# CH32V307_V3_0_0.net
KiCad netlist of a schematic drawn in EasyEDA Pro
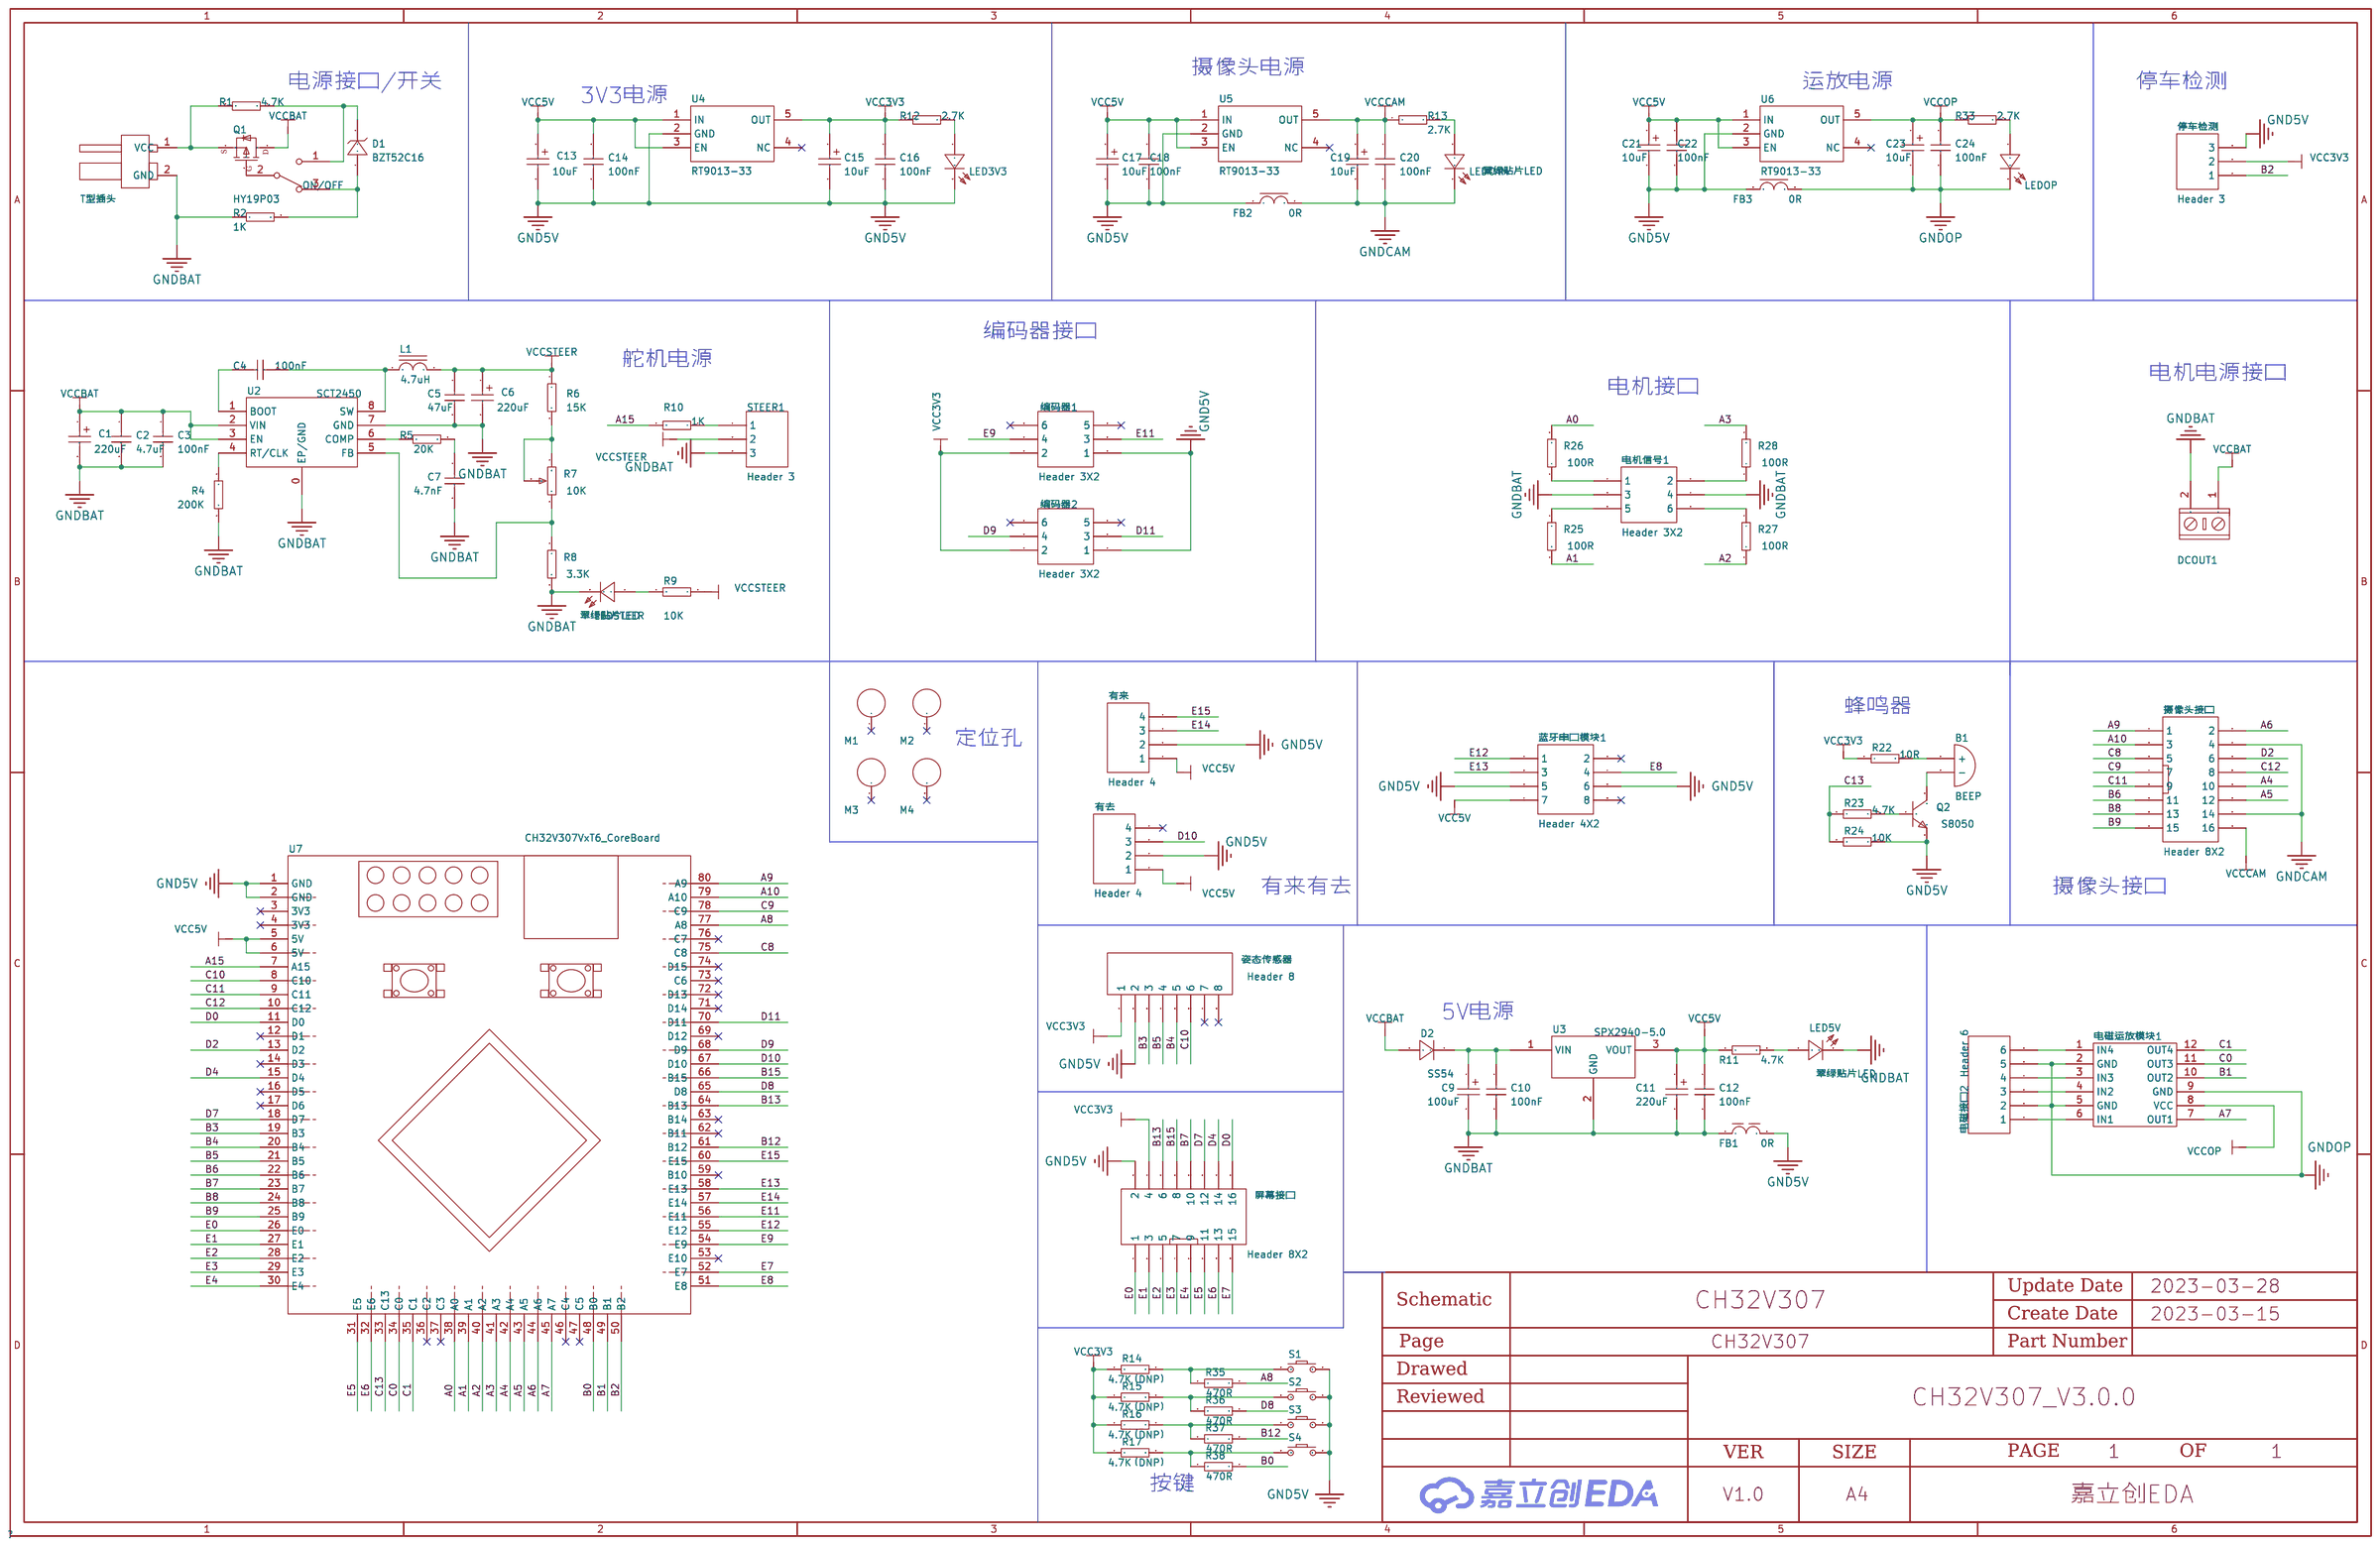
[diagram p0: schematic sheet]

(export (version "E")
  (design (tool "Eeschema 10.0.6"))
  (components
    (comp (ref "B1")
      (value "BEEP")
      (footprint "easyedapro:BEEP 9x5.5mm")
      (libsource (lib "easyedapro") (part "BEEP"))
    )
    (comp (ref "C1")
      (value "220uF")
      (footprint "easyedapro:CAPS6.3")
      (libsource (lib "easyedapro") (part "Cap-Solid_1"))
    )
    (comp (ref "C2")
      (value "4.7nF")
      (footprint "easyedapro:CAPC1608[0603]S-N")
      (libsource (lib "easyedapro") (part "Cap-Chip_3"))
    )
    (comp (ref "C3")
      (value "100nF")
      (footprint "easyedapro:CAPC1608[0603]S-N")
      (libsource (lib "easyedapro") (part "Cap-Chip"))
    )
    (comp (ref "C4")
      (value "100nF")
      (footprint "easyedapro:CAPC1608[0603]S-N")
      (libsource (lib "easyedapro") (part "Cap-Chip"))
    )
    (comp (ref "C5")
      (value "47uF")
      (footprint "easyedapro:CAPC3216[1206]S")
      (libsource (lib "easyedapro") (part "Cap-Chip_2"))
    )
    (comp (ref "C6")
      (value "220uF")
      (footprint "easyedapro:CAPS6.3")
      (libsource (lib "easyedapro") (part "Cap-Solid_1"))
    )
    (comp (ref "C7")
      (value "4.7nF")
      (footprint "easyedapro:CAPC1608[0603]S-N")
      (libsource (lib "easyedapro") (part "Cap-Chip_3"))
    )
    (comp (ref "C9")
      (value "100uF")
      (footprint "easyedapro:CAPS6.3")
      (libsource (lib "easyedapro") (part "Cap-Solid"))
    )
    (comp (ref "C10")
      (value "100nF")
      (footprint "easyedapro:CAPC1608[0603]S-N")
      (libsource (lib "easyedapro") (part "Cap-Chip"))
    )
    (comp (ref "C11")
      (value "220uF")
      (footprint "easyedapro:CAPS6.3")
      (libsource (lib "easyedapro") (part "Cap-Solid_1"))
    )
    (comp (ref "C12")
      (value "100nF")
      (footprint "easyedapro:CAPC1608[0603]S-N")
      (libsource (lib "easyedapro") (part "Cap-Chip"))
    )
    (comp (ref "C13")
      (value "10uF")
      (footprint "easyedapro:CAPT3216")
      (libsource (lib "easyedapro") (part "Cap-Tan"))
    )
    (comp (ref "C14")
      (value "100nF")
      (footprint "easyedapro:CAPC1608[0603]S-N")
      (libsource (lib "easyedapro") (part "Cap-Chip"))
    )
    (comp (ref "C15")
      (value "10uF")
      (footprint "easyedapro:CAPT3216")
      (libsource (lib "easyedapro") (part "Cap-Tan"))
    )
    (comp (ref "C16")
      (value "100nF")
      (footprint "easyedapro:CAPC1608[0603]S-N")
      (libsource (lib "easyedapro") (part "Cap-Chip"))
    )
    (comp (ref "C17")
      (value "10uF")
      (footprint "easyedapro:CAPT3216")
      (libsource (lib "easyedapro") (part "Cap-Tan"))
    )
    (comp (ref "C18")
      (value "100nF")
      (footprint "easyedapro:CAPC1608[0603]S-N")
      (libsource (lib "easyedapro") (part "Cap-Chip"))
    )
    (comp (ref "C19")
      (value "10uF")
      (footprint "easyedapro:CAPT3216")
      (libsource (lib "easyedapro") (part "Cap-Tan"))
    )
    (comp (ref "C20")
      (value "100nF")
      (footprint "easyedapro:CAPC1608[0603]S-N")
      (libsource (lib "easyedapro") (part "Cap-Chip"))
    )
    (comp (ref "C21")
      (value "10uF")
      (footprint "easyedapro:CAPT3216")
      (libsource (lib "easyedapro") (part "Cap-Tan"))
    )
    (comp (ref "C22")
      (value "100nF")
      (footprint "easyedapro:CAPC1608[0603]S-N")
      (libsource (lib "easyedapro") (part "Cap-Chip"))
    )
    (comp (ref "C23")
      (value "10uF")
      (footprint "easyedapro:CAPT3216")
      (libsource (lib "easyedapro") (part "Cap-Tan"))
    )
    (comp (ref "C24")
      (value "100nF")
      (footprint "easyedapro:CAPC1608[0603]S-N")
      (libsource (lib "easyedapro") (part "Cap-Chip"))
    )
    (comp (ref "D1")
      (value "BZT52C16")
      (footprint "easyedapro:SOD-123-L")
      (libsource (lib "easyedapro") (part "Diode TVS Uni-Dir"))
    )
    (comp (ref "D2")
      (value "SS54")
      (footprint "easyedapro:SMA[DO-214AC]")
      (libsource (lib "easyedapro") (part "Diode"))
    )
    (comp (ref "DCOUT1")
      (value "KF/WJ/DG 30x connecter")
      (footprint "easyedapro:KF/WJ/DG 301-2p-5.0mm")
      (libsource (lib "easyedapro") (part "KF/WJ/DG 30x"))
    )
    (comp (ref "FB1")
      (value "0R")
      (footprint "easyedapro:INDC2012[0805]S")
      (libsource (lib "easyedapro") (part "Ind Chip 2"))
    )
    (comp (ref "FB2")
      (value "0R")
      (footprint "easyedapro:INDC2012[0805]S")
      (libsource (lib "easyedapro") (part "Ind-Chip"))
    )
    (comp (ref "FB3")
      (value "0R")
      (footprint "easyedapro:INDC2012[0805]S")
      (libsource (lib "easyedapro") (part "Ind-Chip"))
    )
    (comp (ref "L1")
      (value "4.7uH")
      (footprint "easyedapro:0630 TPC 7*7*3")
      (libsource (lib "easyedapro") (part "Ind-Power"))
    )
    (comp (ref "LED3V3")
      (value "翠绿贴片LED")
      (footprint "easyedapro:LEDC1608(0603)")
      (libsource (lib "easyedapro") (part "LED Chip Green"))
    )
    (comp (ref "LED5V")
      (value "翠绿贴片LED")
      (footprint "easyedapro:LEDC1608(0603)")
      (libsource (lib "easyedapro") (part "LED Chip Green"))
    )
    (comp (ref "LEDCAM")
      (value "翠绿贴片LED")
      (footprint "easyedapro:LEDC1608(0603)")
      (libsource (lib "easyedapro") (part "LED Chip Green"))
    )
    (comp (ref "LEDOP")
      (value "翠绿贴片LED")
      (footprint "easyedapro:LEDC1608(0603)")
      (libsource (lib "easyedapro") (part "LED Chip Green"))
    )
    (comp (ref "LEDSTEER")
      (value "翠绿贴片LED")
      (footprint "easyedapro:LEDC1608(0603)")
      (libsource (lib "easyedapro") (part "LED Chip Green"))
    )
    (comp (ref "M1")
      (value "MountHole")
      (footprint "easyedapro:M3-MountHole-Plated")
      (libsource (lib "easyedapro") (part "MountHole"))
    )
    (comp (ref "M2")
      (value "MountHole")
      (footprint "easyedapro:M3-MountHole-Plated")
      (libsource (lib "easyedapro") (part "MountHole"))
    )
    (comp (ref "M3")
      (value "MountHole")
      (footprint "easyedapro:M3-MountHole-Plated")
      (libsource (lib "easyedapro") (part "MountHole"))
    )
    (comp (ref "M4")
      (value "MountHole")
      (footprint "easyedapro:M3-MountHole-Plated")
      (libsource (lib "easyedapro") (part "MountHole"))
    )
    (comp (ref "ON/OFF")
      (value "SW-SPDT")
      (footprint "easyedapro:SS12D10")
      (libsource (lib "easyedapro") (part "SW-SPDT"))
    )
    (comp (ref "Q1")
      (value "HY19P03")
      (footprint "easyedapro:TO-252AA")
      (libsource (lib "easyedapro") (part "HY19P03"))
    )
    (comp (ref "Q2")
      (value "S8050")
      (footprint "easyedapro:SOT-23")
      (libsource (lib "easyedapro") (part "NPN S8050"))
    )
    (comp (ref "R1")
      (value "4.7K")
      (footprint "easyedapro:RESC1608[0603]S-N")
      (libsource (lib "easyedapro") (part "Res-Chip_2"))
    )
    (comp (ref "R2")
      (value "1K")
      (footprint "easyedapro:RESC1608[0603]S-N")
      (libsource (lib "easyedapro") (part "Res-Chip_1"))
    )
    (comp (ref "R4")
      (value "200K")
      (footprint "easyedapro:RESC1608[0603]S-N")
      (libsource (lib "easyedapro") (part "Res-Chip_4"))
    )
    (comp (ref "R5")
      (value "20K")
      (footprint "easyedapro:RESC1608[0603]S-N")
      (libsource (lib "easyedapro") (part "Res-Chip_5"))
    )
    (comp (ref "R6")
      (value "15K")
      (footprint "easyedapro:RESC1608[0603]S-N")
      (libsource (lib "easyedapro") (part "Res-Chip_6"))
    )
    (comp (ref "R7")
      (value "10K")
      (footprint "easyedapro:RESPOT3296")
      (libsource (lib "easyedapro") (part "Res-Adj-3p"))
    )
    (comp (ref "R8")
      (value "3.3K")
      (footprint "easyedapro:RESC1608[0603]S-N")
      (libsource (lib "easyedapro") (part "Res-Chip_7"))
    )
    (comp (ref "R9")
      (value "10K")
      (footprint "easyedapro:RESC1608[0603]S-N")
      (libsource (lib "easyedapro") (part "Res-Chip"))
    )
    (comp (ref "R10")
      (value "1K")
      (footprint "easyedapro:RESC1608[0603]S-N")
      (libsource (lib "easyedapro") (part "Res-Chip_1"))
    )
    (comp (ref "R11")
      (value "4.7K")
      (footprint "easyedapro:RESC1608[0603]S-N")
      (libsource (lib "easyedapro") (part "Res-Chip_2"))
    )
    (comp (ref "R12")
      (value "2.7K")
      (footprint "easyedapro:RESC1608[0603]S-N")
      (libsource (lib "easyedapro") (part "Res-Chip_3"))
    )
    (comp (ref "R13")
      (value "2.7K")
      (footprint "easyedapro:RESC1608[0603]S-N")
      (libsource (lib "easyedapro") (part "Res-Chip_3"))
    )
    (comp (ref "R14")
      (value "4.7K(DNP)")
      (footprint "easyedapro:RESC1608[0603]S-N")
      (libsource (lib "easyedapro") (part "Res-Chip_9"))
    )
    (comp (ref "R15")
      (value "4.7K(DNP)")
      (footprint "easyedapro:RESC1608[0603]S-N")
      (libsource (lib "easyedapro") (part "Res-Chip_9"))
    )
    (comp (ref "R16")
      (value "4.7K(DNP)")
      (footprint "easyedapro:RESC1608[0603]S-N")
      (libsource (lib "easyedapro") (part "Res-Chip_9"))
    )
    (comp (ref "R17")
      (value "4.7K(DNP)")
      (footprint "easyedapro:RESC1608[0603]S-N")
      (libsource (lib "easyedapro") (part "Res-Chip_9"))
    )
    (comp (ref "R22")
      (value "10R")
      (footprint "easyedapro:RESC1608[0603]S-N")
      (libsource (lib "easyedapro") (part "Res-Chip_10"))
    )
    (comp (ref "R23")
      (value "4.7K")
      (footprint "easyedapro:RESC1608[0603]S-N")
      (libsource (lib "easyedapro") (part "Res-Chip_2"))
    )
    (comp (ref "R24")
      (value "10K")
      (footprint "easyedapro:RESC1608[0603]S-N")
      (libsource (lib "easyedapro") (part "Res-Chip"))
    )
    (comp (ref "R25")
      (value "100R")
      (footprint "easyedapro:RESC1608[0603]S-N")
      (libsource (lib "easyedapro") (part "Res-Chip_8"))
    )
    (comp (ref "R26")
      (value "100R")
      (footprint "easyedapro:RESC1608[0603]S-N")
      (libsource (lib "easyedapro") (part "Res-Chip_8"))
    )
    (comp (ref "R27")
      (value "100R")
      (footprint "easyedapro:RESC1608[0603]S-N")
      (libsource (lib "easyedapro") (part "Res-Chip_8"))
    )
    (comp (ref "R28")
      (value "100R")
      (footprint "easyedapro:RESC1608[0603]S-N")
      (libsource (lib "easyedapro") (part "Res-Chip_8"))
    )
    (comp (ref "R33")
      (value "2.7K")
      (footprint "easyedapro:RESC1608[0603]S-N")
      (libsource (lib "easyedapro") (part "Res-Chip_3"))
    )
    (comp (ref "R35")
      (value "470R")
      (footprint "easyedapro:RESC1608[0603]S-N")
      (libsource (lib "easyedapro") (part "Res-Chip_11"))
    )
    (comp (ref "R36")
      (value "470R")
      (footprint "easyedapro:RESC1608[0603]S-N")
      (libsource (lib "easyedapro") (part "Res-Chip_11"))
    )
    (comp (ref "R37")
      (value "470R")
      (footprint "easyedapro:RESC1608[0603]S-N")
      (libsource (lib "easyedapro") (part "Res-Chip_11"))
    )
    (comp (ref "R38")
      (value "470R")
      (footprint "easyedapro:RESC1608[0603]S-N")
      (libsource (lib "easyedapro") (part "Res-Chip_11"))
    )
    (comp (ref "S1")
      (value "Button")
      (footprint "easyedapro:PTS810-3*4-CurvePin")
      (libsource (lib "easyedapro") (part "KEY"))
    )
    (comp (ref "S2")
      (value "Button")
      (footprint "easyedapro:PTS810-3*4-CurvePin")
      (libsource (lib "easyedapro") (part "KEY"))
    )
    (comp (ref "S3")
      (value "Button")
      (footprint "easyedapro:PTS810-3*4-CurvePin")
      (libsource (lib "easyedapro") (part "KEY"))
    )
    (comp (ref "S4")
      (value "Button")
      (footprint "easyedapro:PTS810-3*4-CurvePin")
      (libsource (lib "easyedapro") (part "KEY"))
    )
    (comp (ref "STEER1")
      (value "Header 3")
      (footprint "easyedapro:HDR1X3")
      (libsource (lib "easyedapro") (part "Header 3"))
    )
    (comp (ref "U1")
      (value "T型插头")
      (footprint "easyedapro:Wired T-Header ThroughHole")
      (libsource (lib "easyedapro") (part "T_Header"))
    )
    (comp (ref "U2")
      (value "SCT2450")
      (footprint "easyedapro:SOP-8E")
      (libsource (lib "easyedapro") (part "SCT2450"))
    )
    (comp (ref "U3")
      (value "SPX2940-5.0")
      (footprint "easyedapro:TO-263-3")
      (libsource (lib "easyedapro") (part "LM2940-5.0"))
    )
    (comp (ref "U4")
      (value "RT9013-33")
      (footprint "easyedapro:SOT-23-5")
      (libsource (lib "easyedapro") (part "RT9013-33"))
    )
    (comp (ref "U5")
      (value "RT9013-33")
      (footprint "easyedapro:SOT-23-5")
      (libsource (lib "easyedapro") (part "RT9013-33"))
    )
    (comp (ref "U6")
      (value "RT9013-33")
      (footprint "easyedapro:SOT-23-5")
      (libsource (lib "easyedapro") (part "RT9013-33"))
    )
    (comp (ref "U7")
      (value "CH32V307VxT6_CoreBoard")
      (footprint "easyedapro:CH32V307VxT6_CoreBoard")
      (libsource (lib "easyedapro") (part "CH32V307VxT6_CoreBoardV1.3"))
    )
    (comp (ref "停车检测")
      (value "Header 3")
      (footprint "easyedapro:HDR1X3")
      (libsource (lib "easyedapro") (part "Header 3"))
    )
    (comp (ref "姿态传感器")
      (value "Header 8")
      (footprint "easyedapro:HDR1X8")
      (libsource (lib "easyedapro") (part "Header 8"))
    )
    (comp (ref "屏幕接口")
      (value "Header 8X2")
      (footprint "easyedapro:HDR2X8-M-SMT")
      (libsource (lib "easyedapro") (part "Header 8X2"))
    )
    (comp (ref "摄像头接口")
      (value "Header 8X2")
      (footprint "easyedapro:HDR2X8-M-SMT")
      (libsource (lib "easyedapro") (part "Header 8X2"))
    )
    (comp (ref "有去")
      (value "Header 4")
      (footprint "easyedapro:HDR1X4")
      (libsource (lib "easyedapro") (part "Header 4"))
    )
    (comp (ref "有来")
      (value "Header 4")
      (footprint "easyedapro:HDR1X4")
      (libsource (lib "easyedapro") (part "Header 4"))
    )
    (comp (ref "电机信号1")
      (value "Header 3X2")
      (footprint "easyedapro:HDR2X3-M-SMT")
      (libsource (lib "easyedapro") (part "Header 3X2"))
    )
    (comp (ref "电磁接口2")
      (value "Header 6")
      (footprint "easyedapro:HDR1X6")
      (libsource (lib "easyedapro") (part "Header 6"))
    )
    (comp (ref "电磁运放模块1")
      (value "OPA_MOD")
      (footprint "easyedapro:SEEKFREE_4CHANEL_OPAMOD")
      (libsource (lib "easyedapro") (part "OPA_4CHANNEL_SEEKFREE"))
    )
    (comp (ref "编码器1")
      (value "Header 3X2")
      (footprint "easyedapro:HDR2X3-M-SMT")
      (libsource (lib "easyedapro") (part "Header 3X2"))
    )
    (comp (ref "编码器2")
      (value "Header 3X2")
      (footprint "easyedapro:HDR2X3-M-SMT")
      (libsource (lib "easyedapro") (part "Header 3X2"))
    )
    (comp (ref "蓝牙串口模块1")
      (value "Header 4X2")
      (footprint "easyedapro:Female-Header-2.54-SMD-8")
      (libsource (lib "easyedapro") (part "Header 4X2"))
    )
  )
  (nets
    (net (code "1") (name "/A0") (class "Default")
      (node (ref "R26") (pin "2") (pinfunction "2_2") (pintype "input"))
      (node (ref "U7") (pin "38") (pinfunction "A0_38") (pintype "input"))
    )
    (net (code "2") (name "/A1") (class "Default")
      (node (ref "R25") (pin "2") (pinfunction "2_2") (pintype "input"))
      (node (ref "U7") (pin "39") (pinfunction "A1_39") (pintype "input"))
    )
    (net (code "3") (name "/A2") (class "Default")
      (node (ref "R27") (pin "2") (pinfunction "2_2") (pintype "input"))
      (node (ref "U7") (pin "40") (pinfunction "A2_40") (pintype "input"))
    )
    (net (code "4") (name "/A3") (class "Default")
      (node (ref "R28") (pin "2") (pinfunction "2_2") (pintype "input"))
      (node (ref "U7") (pin "41") (pinfunction "A3_41") (pintype "input"))
    )
    (net (code "5") (name "/A4") (class "Default")
      (node (ref "U7") (pin "42") (pinfunction "A4_42") (pintype "input"))
      (node (ref "摄像头接口") (pin "10") (pinfunction "10_10") (pintype "input"))
    )
    (net (code "6") (name "/A5") (class "Default")
      (node (ref "U7") (pin "43") (pinfunction "A5_43") (pintype "input"))
      (node (ref "摄像头接口") (pin "12") (pinfunction "12_12") (pintype "input"))
    )
    (net (code "7") (name "/A6") (class "Default")
      (node (ref "U7") (pin "44") (pinfunction "A6_44") (pintype "input"))
      (node (ref "摄像头接口") (pin "2") (pinfunction "2_2") (pintype "input"))
    )
    (net (code "8") (name "/A7") (class "Default")
      (node (ref "U7") (pin "45") (pinfunction "A7_45") (pintype "input"))
      (node (ref "电磁运放模块1") (pin "7") (pinfunction "OUT1_7") (pintype "input"))
    )
    (net (code "9") (name "/A8") (class "Default")
      (node (ref "R35") (pin "2") (pinfunction "2_2") (pintype "input"))
      (node (ref "U7") (pin "77") (pinfunction "A8_77") (pintype "input"))
    )
    (net (code "10") (name "/A9") (class "Default")
      (node (ref "U7") (pin "80") (pinfunction "A9_80") (pintype "input"))
      (node (ref "摄像头接口") (pin "1") (pinfunction "1_1") (pintype "input"))
    )
    (net (code "11") (name "/A10") (class "Default")
      (node (ref "U7") (pin "79") (pinfunction "A10_79") (pintype "input"))
      (node (ref "摄像头接口") (pin "3") (pinfunction "3_3") (pintype "input"))
    )
    (net (code "12") (name "/A15") (class "Default")
      (node (ref "R10") (pin "2") (pinfunction "2_2") (pintype "input"))
      (node (ref "U7") (pin "7") (pinfunction "A15_7") (pintype "input"))
    )
    (net (code "13") (name "/B0") (class "Default")
      (node (ref "R38") (pin "2") (pinfunction "2_2") (pintype "input"))
      (node (ref "U7") (pin "48") (pinfunction "B0_48") (pintype "input"))
    )
    (net (code "14") (name "/B1") (class "Default")
      (node (ref "U7") (pin "49") (pinfunction "B1_49") (pintype "input"))
      (node (ref "电磁运放模块1") (pin "10") (pinfunction "OUT2_10") (pintype "input"))
    )
    (net (code "15") (name "/B2") (class "Default")
      (node (ref "U7") (pin "50") (pinfunction "B2_50") (pintype "input"))
      (node (ref "停车检测") (pin "1") (pinfunction "1_1") (pintype "input"))
    )
    (net (code "16") (name "/B3") (class "Default")
      (node (ref "U7") (pin "19") (pinfunction "B3_19") (pintype "input"))
      (node (ref "姿态传感器") (pin "3") (pinfunction "3_3") (pintype "input"))
    )
    (net (code "17") (name "/B4") (class "Default")
      (node (ref "U7") (pin "20") (pinfunction "B4_20") (pintype "input"))
      (node (ref "姿态传感器") (pin "5") (pinfunction "5_5") (pintype "input"))
    )
    (net (code "18") (name "/B5") (class "Default")
      (node (ref "U7") (pin "21") (pinfunction "B5_21") (pintype "input"))
      (node (ref "姿态传感器") (pin "4") (pinfunction "4_4") (pintype "input"))
    )
    (net (code "19") (name "/B6") (class "Default")
      (node (ref "U7") (pin "22") (pinfunction "B6_22") (pintype "input"))
      (node (ref "摄像头接口") (pin "11") (pinfunction "11_11") (pintype "input"))
    )
    (net (code "20") (name "/B7") (class "Default")
      (node (ref "U7") (pin "23") (pinfunction "B7_23") (pintype "input"))
      (node (ref "屏幕接口") (pin "10") (pinfunction "10_10") (pintype "input"))
    )
    (net (code "21") (name "/B8") (class "Default")
      (node (ref "U7") (pin "24") (pinfunction "B8_24") (pintype "input"))
      (node (ref "摄像头接口") (pin "13") (pinfunction "13_13") (pintype "input"))
    )
    (net (code "22") (name "/B9") (class "Default")
      (node (ref "U7") (pin "25") (pinfunction "B9_25") (pintype "input"))
      (node (ref "摄像头接口") (pin "15") (pinfunction "15_15") (pintype "input"))
    )
    (net (code "23") (name "/B12") (class "Default")
      (node (ref "R37") (pin "2") (pinfunction "2_2") (pintype "input"))
      (node (ref "U7") (pin "61") (pinfunction "B12_61") (pintype "input"))
    )
    (net (code "24") (name "/B13") (class "Default")
      (node (ref "U7") (pin "64") (pinfunction "B13_64") (pintype "input"))
      (node (ref "屏幕接口") (pin "6") (pinfunction "6_6") (pintype "input"))
    )
    (net (code "25") (name "/B15") (class "Default")
      (node (ref "U7") (pin "66") (pinfunction "B15_66") (pintype "input"))
      (node (ref "屏幕接口") (pin "8") (pinfunction "8_8") (pintype "input"))
    )
    (net (code "26") (name "/C0") (class "Default")
      (node (ref "U7") (pin "34") (pinfunction "C0_34") (pintype "input"))
      (node (ref "电磁运放模块1") (pin "11") (pinfunction "OUT3_11") (pintype "input"))
    )
    (net (code "27") (name "/C1") (class "Default")
      (node (ref "U7") (pin "35") (pinfunction "C1_35") (pintype "input"))
      (node (ref "电磁运放模块1") (pin "12") (pinfunction "OUT4_12") (pintype "input"))
    )
    (net (code "28") (name "/C8") (class "Default")
      (node (ref "U7") (pin "75") (pinfunction "C8_75") (pintype "input"))
      (node (ref "摄像头接口") (pin "5") (pinfunction "5_5") (pintype "input"))
    )
    (net (code "29") (name "/C9") (class "Default")
      (node (ref "U7") (pin "78") (pinfunction "C9_78") (pintype "input"))
      (node (ref "摄像头接口") (pin "7") (pinfunction "7_7") (pintype "input"))
    )
    (net (code "30") (name "/C10") (class "Default")
      (node (ref "U7") (pin "8") (pinfunction "C10_8") (pintype "input"))
      (node (ref "姿态传感器") (pin "6") (pinfunction "6_6") (pintype "input"))
    )
    (net (code "31") (name "/C11") (class "Default")
      (node (ref "U7") (pin "9") (pinfunction "C11_9") (pintype "input"))
      (node (ref "摄像头接口") (pin "9") (pinfunction "9_9") (pintype "input"))
    )
    (net (code "32") (name "/C12") (class "Default")
      (node (ref "U7") (pin "10") (pinfunction "C12_10") (pintype "input"))
      (node (ref "摄像头接口") (pin "8") (pinfunction "8_8") (pintype "input"))
    )
    (net (code "33") (name "/C13") (class "Default")
      (node (ref "R23") (pin "1") (pinfunction "1_1") (pintype "input"))
      (node (ref "R24") (pin "1") (pinfunction "1_1") (pintype "input"))
      (node (ref "U7") (pin "33") (pinfunction "C13_33") (pintype "input"))
    )
    (net (code "34") (name "/D0") (class "Default")
      (node (ref "U7") (pin "11") (pinfunction "D0_11") (pintype "input"))
      (node (ref "屏幕接口") (pin "16") (pinfunction "16_16") (pintype "input"))
    )
    (net (code "35") (name "/D2") (class "Default")
      (node (ref "U7") (pin "13") (pinfunction "D2_13") (pintype "input"))
      (node (ref "摄像头接口") (pin "6") (pinfunction "6_6") (pintype "input"))
    )
    (net (code "36") (name "/D4") (class "Default")
      (node (ref "U7") (pin "15") (pinfunction "D4_15") (pintype "input"))
      (node (ref "屏幕接口") (pin "14") (pinfunction "14_14") (pintype "input"))
    )
    (net (code "37") (name "/D7") (class "Default")
      (node (ref "U7") (pin "18") (pinfunction "D7_18") (pintype "input"))
      (node (ref "屏幕接口") (pin "12") (pinfunction "12_12") (pintype "input"))
    )
    (net (code "38") (name "/D8") (class "Default")
      (node (ref "R36") (pin "2") (pinfunction "2_2") (pintype "input"))
      (node (ref "U7") (pin "65") (pinfunction "D8_65") (pintype "input"))
    )
    (net (code "39") (name "/D9") (class "Default")
      (node (ref "U7") (pin "68") (pinfunction "D9_68") (pintype "input"))
      (node (ref "编码器2") (pin "4") (pinfunction "4_4") (pintype "input"))
    )
    (net (code "40") (name "/D10") (class "Default")
      (node (ref "U7") (pin "67") (pinfunction "D10_67") (pintype "input"))
      (node (ref "有去") (pin "3") (pinfunction "3_3") (pintype "input"))
    )
    (net (code "41") (name "/D11") (class "Default")
      (node (ref "U7") (pin "70") (pinfunction "D11_70") (pintype "input"))
      (node (ref "编码器2") (pin "3") (pinfunction "3_3") (pintype "input"))
    )
    (net (code "42") (name "/E0") (class "Default")
      (node (ref "U7") (pin "26") (pinfunction "E0_26") (pintype "input"))
      (node (ref "屏幕接口") (pin "1") (pinfunction "1_1") (pintype "input"))
    )
    (net (code "43") (name "/E1") (class "Default")
      (node (ref "U7") (pin "27") (pinfunction "E1_27") (pintype "input"))
      (node (ref "屏幕接口") (pin "3") (pinfunction "3_3") (pintype "input"))
    )
    (net (code "44") (name "/E2") (class "Default")
      (node (ref "U7") (pin "28") (pinfunction "E2_28") (pintype "input"))
      (node (ref "屏幕接口") (pin "5") (pinfunction "5_5") (pintype "input"))
    )
    (net (code "45") (name "/E3") (class "Default")
      (node (ref "U7") (pin "29") (pinfunction "E3_29") (pintype "input"))
      (node (ref "屏幕接口") (pin "7") (pinfunction "7_7") (pintype "input"))
    )
    (net (code "46") (name "/E4") (class "Default")
      (node (ref "U7") (pin "30") (pinfunction "E4_30") (pintype "input"))
      (node (ref "屏幕接口") (pin "9") (pinfunction "9_9") (pintype "input"))
    )
    (net (code "47") (name "/E5") (class "Default")
      (node (ref "U7") (pin "31") (pinfunction "E5_31") (pintype "input"))
      (node (ref "屏幕接口") (pin "11") (pinfunction "11_11") (pintype "input"))
    )
    (net (code "48") (name "/E6") (class "Default")
      (node (ref "U7") (pin "32") (pinfunction "E6_32") (pintype "input"))
      (node (ref "屏幕接口") (pin "13") (pinfunction "13_13") (pintype "input"))
    )
    (net (code "49") (name "/E7") (class "Default")
      (node (ref "U7") (pin "52") (pinfunction "E7_52") (pintype "input"))
      (node (ref "屏幕接口") (pin "15") (pinfunction "15_15") (pintype "input"))
    )
    (net (code "50") (name "/E8") (class "Default")
      (node (ref "U7") (pin "51") (pinfunction "E8_51") (pintype "input"))
      (node (ref "蓝牙串口模块1") (pin "4") (pinfunction "4_4") (pintype "input"))
    )
    (net (code "51") (name "/E9") (class "Default")
      (node (ref "U7") (pin "54") (pinfunction "E9_54") (pintype "input"))
      (node (ref "编码器1") (pin "4") (pinfunction "4_4") (pintype "input"))
    )
    (net (code "52") (name "/E11") (class "Default")
      (node (ref "U7") (pin "56") (pinfunction "E11_56") (pintype "input"))
      (node (ref "编码器1") (pin "3") (pinfunction "3_3") (pintype "input"))
    )
    (net (code "53") (name "/E12") (class "Default")
      (node (ref "U7") (pin "55") (pinfunction "E12_55") (pintype "input"))
      (node (ref "蓝牙串口模块1") (pin "1") (pinfunction "1_1") (pintype "input"))
    )
    (net (code "54") (name "/E13") (class "Default")
      (node (ref "U7") (pin "58") (pinfunction "E13_58") (pintype "input"))
      (node (ref "蓝牙串口模块1") (pin "3") (pinfunction "3_3") (pintype "input"))
    )
    (net (code "55") (name "/E14") (class "Default")
      (node (ref "U7") (pin "57") (pinfunction "E14_57") (pintype "input"))
      (node (ref "有来") (pin "3") (pinfunction "3_3") (pintype "input"))
    )
    (net (code "56") (name "/E15") (class "Default")
      (node (ref "U7") (pin "60") (pinfunction "E15_60") (pintype "input"))
      (node (ref "有来") (pin "4") (pinfunction "4_4") (pintype "input"))
    )
    (net (code "57") (name "GND5V") (class "Default")
      (node (ref "C13") (pin "2") (pinfunction "2_2") (pintype "input"))
      (node (ref "C14") (pin "2") (pinfunction "2_2") (pintype "input"))
      (node (ref "C15") (pin "2") (pinfunction "2_2") (pintype "input"))
      (node (ref "C16") (pin "2") (pinfunction "2_2") (pintype "input"))
      (node (ref "C17") (pin "2") (pinfunction "2_2") (pintype "input"))
      (node (ref "C18") (pin "2") (pinfunction "2_2") (pintype "input"))
      (node (ref "C21") (pin "2") (pinfunction "2_2") (pintype "input"))
      (node (ref "C22") (pin "2") (pinfunction "2_2") (pintype "input"))
      (node (ref "FB1") (pin "2") (pinfunction "2_2") (pintype "input"))
      (node (ref "FB2") (pin "1") (pinfunction "1_1") (pintype "input"))
      (node (ref "FB3") (pin "1") (pinfunction "1_1") (pintype "input"))
      (node (ref "LED3V3") (pin "C") (pinfunction "C_C") (pintype "input"))
      (node (ref "Q2") (pin "2") (pinfunction "E_2") (pintype "input"))
      (node (ref "R24") (pin "2") (pinfunction "2_2") (pintype "input"))
      (node (ref "S1") (pin "1") (pinfunction "1_1") (pintype "input"))
      (node (ref "S2") (pin "1") (pinfunction "1_1") (pintype "input"))
      (node (ref "S3") (pin "1") (pinfunction "1_1") (pintype "input"))
      (node (ref "S4") (pin "1") (pinfunction "1_1") (pintype "input"))
      (node (ref "U4") (pin "2") (pinfunction "GND_2") (pintype "input"))
      (node (ref "U5") (pin "2") (pinfunction "GND_2") (pintype "input"))
      (node (ref "U6") (pin "2") (pinfunction "GND_2") (pintype "input"))
      (node (ref "U7") (pin "1") (pinfunction "GND_1") (pintype "input"))
      (node (ref "U7") (pin "2") (pinfunction "GND_2") (pintype "input"))
      (node (ref "停车检测") (pin "3") (pinfunction "3_3") (pintype "input"))
      (node (ref "姿态传感器") (pin "2") (pinfunction "2_2") (pintype "input"))
      (node (ref "屏幕接口") (pin "2") (pinfunction "2_2") (pintype "input"))
      (node (ref "有去") (pin "2") (pinfunction "2_2") (pintype "input"))
      (node (ref "有来") (pin "2") (pinfunction "2_2") (pintype "input"))
      (node (ref "编码器1") (pin "1") (pinfunction "1_1") (pintype "input"))
      (node (ref "编码器2") (pin "1") (pinfunction "1_1") (pintype "input"))
      (node (ref "蓝牙串口模块1") (pin "5") (pinfunction "5_5") (pintype "input"))
      (node (ref "蓝牙串口模块1") (pin "6") (pinfunction "6_6") (pintype "input"))
    )
    (net (code "58") (name "GNDBAT") (class "Default")
      (node (ref "C1") (pin "2") (pinfunction "2_2") (pintype "input"))
      (node (ref "C10") (pin "2") (pinfunction "2_2") (pintype "input"))
      (node (ref "C11") (pin "2") (pinfunction "2_2") (pintype "input"))
      (node (ref "C12") (pin "2") (pinfunction "2_2") (pintype "input"))
      (node (ref "C2") (pin "2") (pinfunction "2_2") (pintype "input"))
      (node (ref "C3") (pin "2") (pinfunction "2_2") (pintype "input"))
      (node (ref "C5") (pin "2") (pinfunction "2_2") (pintype "input"))
      (node (ref "C6") (pin "2") (pinfunction "2_2") (pintype "input"))
      (node (ref "C7") (pin "2") (pinfunction "2_2") (pintype "input"))
      (node (ref "C9") (pin "2") (pinfunction "2_2") (pintype "input"))
      (node (ref "DCOUT1") (pin "2") (pinfunction "2_2") (pintype "input"))
      (node (ref "FB1") (pin "1") (pinfunction "1_1") (pintype "input"))
      (node (ref "LED5V") (pin "C") (pinfunction "C_C") (pintype "input"))
      (node (ref "LEDSTEER") (pin "C") (pinfunction "C_C") (pintype "input"))
      (node (ref "R2") (pin "1") (pinfunction "1_1") (pintype "input"))
      (node (ref "R4") (pin "2") (pinfunction "2_2") (pintype "input"))
      (node (ref "R8") (pin "2") (pinfunction "2_2") (pintype "input"))
      (node (ref "STEER1") (pin "3") (pinfunction "3_3") (pintype "input"))
      (node (ref "U1") (pin "2") (pinfunction "GND_2") (pintype "input"))
      (node (ref "U2") (pin "0") (pinfunction "EP/GND_0") (pintype "input"))
      (node (ref "U2") (pin "7") (pinfunction "GND_7") (pintype "input"))
      (node (ref "U3") (pin "2") (pinfunction "GND_2") (pintype "input"))
      (node (ref "电机信号1") (pin "3") (pinfunction "3_3") (pintype "input"))
      (node (ref "电机信号1") (pin "4") (pinfunction "4_4") (pintype "input"))
    )
    (net (code "59") (name "GNDCAM") (class "Default")
      (node (ref "C19") (pin "2") (pinfunction "2_2") (pintype "input"))
      (node (ref "C20") (pin "2") (pinfunction "2_2") (pintype "input"))
      (node (ref "FB2") (pin "2") (pinfunction "2_2") (pintype "input"))
      (node (ref "LEDCAM") (pin "C") (pinfunction "C_C") (pintype "input"))
      (node (ref "摄像头接口") (pin "14") (pinfunction "14_14") (pintype "input"))
      (node (ref "摄像头接口") (pin "4") (pinfunction "4_4") (pintype "input"))
    )
    (net (code "60") (name "GNDOP") (class "Default")
      (node (ref "C23") (pin "2") (pinfunction "2_2") (pintype "input"))
      (node (ref "C24") (pin "2") (pinfunction "2_2") (pintype "input"))
      (node (ref "FB3") (pin "2") (pinfunction "2_2") (pintype "input"))
      (node (ref "LEDOP") (pin "C") (pinfunction "C_C") (pintype "input"))
      (node (ref "电磁接口2") (pin "2") (pinfunction "2_2") (pintype "input"))
      (node (ref "电磁接口2") (pin "5") (pinfunction "5_5") (pintype "input"))
      (node (ref "电磁运放模块1") (pin "2") (pinfunction "GND_2") (pintype "input"))
      (node (ref "电磁运放模块1") (pin "5") (pinfunction "GND_5") (pintype "input"))
      (node (ref "电磁运放模块1") (pin "9") (pinfunction "GND_9") (pintype "input"))
    )
    (net (code "61") (name "Net-(B1-+)") (class "Default")
      (node (ref "B1") (pin "1") (pinfunction "+_1") (pintype "input"))
      (node (ref "R22") (pin "2") (pinfunction "2_2") (pintype "input"))
    )
    (net (code "62") (name "Net-(B1--)") (class "Default")
      (node (ref "B1") (pin "2") (pinfunction "-_2") (pintype "input"))
      (node (ref "Q2") (pin "3") (pinfunction "C_3") (pintype "input"))
    )
    (net (code "63") (name "Net-(C7-Pad1)") (class "Default")
      (node (ref "C7") (pin "1") (pinfunction "1_1") (pintype "input"))
      (node (ref "R5") (pin "2") (pinfunction "2_2") (pintype "input"))
    )
    (net (code "64") (name "Net-(D1-PadA)") (class "Default")
      (node (ref "D1") (pin "A") (pinfunction "A_A") (pintype "input"))
      (node (ref "ON/OFF") (pin "3") (pintype "input"))
      (node (ref "R2") (pin "2") (pinfunction "2_2") (pintype "input"))
    )
    (net (code "65") (name "Net-(D1-PadK)") (class "Default")
      (node (ref "D1") (pin "K") (pinfunction "K_K") (pintype "input"))
      (node (ref "ON/OFF") (pin "1") (pintype "input"))
      (node (ref "R1") (pin "2") (pinfunction "2_2") (pintype "input"))
    )
    (net (code "66") (name "Net-(LED3V3-PadA)") (class "Default")
      (node (ref "LED3V3") (pin "A") (pinfunction "A_A") (pintype "input"))
      (node (ref "R12") (pin "2") (pinfunction "2_2") (pintype "input"))
    )
    (net (code "67") (name "Net-(LED5V-PadA)") (class "Default")
      (node (ref "LED5V") (pin "A") (pinfunction "A_A") (pintype "input"))
      (node (ref "R11") (pin "2") (pinfunction "2_2") (pintype "input"))
    )
    (net (code "68") (name "Net-(LEDCAM-PadA)") (class "Default")
      (node (ref "LEDCAM") (pin "A") (pinfunction "A_A") (pintype "input"))
      (node (ref "R13") (pin "2") (pinfunction "2_2") (pintype "input"))
    )
    (net (code "69") (name "Net-(LEDOP-PadA)") (class "Default")
      (node (ref "LEDOP") (pin "A") (pinfunction "A_A") (pintype "input"))
      (node (ref "R33") (pin "2") (pinfunction "2_2") (pintype "input"))
    )
    (net (code "70") (name "Net-(LEDSTEER-PadA)") (class "Default")
      (node (ref "LEDSTEER") (pin "A") (pinfunction "A_A") (pintype "input"))
      (node (ref "R9") (pin "1") (pinfunction "1_1") (pintype "input"))
    )
    (net (code "71") (name "Net-(Q1-G)") (class "Default")
      (node (ref "ON/OFF") (pin "2") (pintype "input"))
      (node (ref "Q1") (pin "2") (pinfunction "G_2") (pintype "input"))
    )
    (net (code "72") (name "Net-(Q1-S)") (class "Default")
      (node (ref "Q1") (pin "3") (pinfunction "S_3") (pintype "input"))
      (node (ref "R1") (pin "1") (pinfunction "1_1") (pintype "input"))
      (node (ref "U1") (pin "1") (pinfunction "VCC_1") (pintype "input"))
    )
    (net (code "73") (name "Net-(Q2-B)") (class "Default")
      (node (ref "Q2") (pin "1") (pinfunction "B_1") (pintype "input"))
      (node (ref "R23") (pin "2") (pinfunction "2_2") (pintype "input"))
    )
    (net (code "74") (name "Net-(R7-BOT)") (class "Default")
      (node (ref "R7") (pin "2") (pinfunction "BOT_2") (pintype "input"))
      (node (ref "R8") (pin "1") (pinfunction "1_1") (pintype "input"))
      (node (ref "U2") (pin "5") (pinfunction "FB_5") (pintype "input"))
    )
    (net (code "75") (name "Net-(R7-TOP)") (class "Default")
      (node (ref "R6") (pin "2") (pinfunction "2_2") (pintype "input"))
      (node (ref "R7") (pin "1") (pinfunction "TOP_1") (pintype "input"))
      (node (ref "R7") (pin "ADJ") (pinfunction "ADJ_ADJ") (pintype "input"))
    )
    (net (code "76") (name "Net-(R10-Pad1)") (class "Default")
      (node (ref "R10") (pin "1") (pinfunction "1_1") (pintype "input"))
      (node (ref "STEER1") (pin "1") (pinfunction "1_1") (pintype "input"))
    )
    (net (code "77") (name "Net-(R14-Pad2)") (class "Default")
      (node (ref "R14") (pin "2") (pinfunction "2_2") (pintype "input"))
      (node (ref "R35") (pin "1") (pinfunction "1_1") (pintype "input"))
      (node (ref "S1") (pin "2") (pinfunction "2_2") (pintype "input"))
    )
    (net (code "78") (name "Net-(R15-Pad2)") (class "Default")
      (node (ref "R15") (pin "2") (pinfunction "2_2") (pintype "input"))
      (node (ref "R36") (pin "1") (pinfunction "1_1") (pintype "input"))
      (node (ref "S2") (pin "2") (pinfunction "2_2") (pintype "input"))
    )
    (net (code "79") (name "Net-(R16-Pad2)") (class "Default")
      (node (ref "R16") (pin "2") (pinfunction "2_2") (pintype "input"))
      (node (ref "R37") (pin "1") (pinfunction "1_1") (pintype "input"))
      (node (ref "S3") (pin "2") (pinfunction "2_2") (pintype "input"))
    )
    (net (code "80") (name "Net-(R17-Pad2)") (class "Default")
      (node (ref "R17") (pin "2") (pinfunction "2_2") (pintype "input"))
      (node (ref "R38") (pin "1") (pinfunction "1_1") (pintype "input"))
      (node (ref "S4") (pin "2") (pinfunction "2_2") (pintype "input"))
    )
    (net (code "81") (name "Net-(R25-Pad1)") (class "Default")
      (node (ref "R25") (pin "1") (pinfunction "1_1") (pintype "input"))
      (node (ref "电机信号1") (pin "5") (pinfunction "5_5") (pintype "input"))
    )
    (net (code "82") (name "Net-(R26-Pad1)") (class "Default")
      (node (ref "R26") (pin "1") (pinfunction "1_1") (pintype "input"))
      (node (ref "电机信号1") (pin "1") (pinfunction "1_1") (pintype "input"))
    )
    (net (code "83") (name "Net-(R27-Pad1)") (class "Default")
      (node (ref "R27") (pin "1") (pinfunction "1_1") (pintype "input"))
      (node (ref "电机信号1") (pin "6") (pinfunction "6_6") (pintype "input"))
    )
    (net (code "84") (name "Net-(R28-Pad1)") (class "Default")
      (node (ref "R28") (pin "1") (pinfunction "1_1") (pintype "input"))
      (node (ref "电机信号1") (pin "2") (pinfunction "2_2") (pintype "input"))
    )
    (net (code "85") (name "Net-(U2-BOOT)") (class "Default")
      (node (ref "C4") (pin "1") (pinfunction "1_1") (pintype "input"))
      (node (ref "U2") (pin "1") (pinfunction "BOOT_1") (pintype "input"))
    )
    (net (code "86") (name "Net-(U2-COMP)") (class "Default")
      (node (ref "R5") (pin "1") (pinfunction "1_1") (pintype "input"))
      (node (ref "U2") (pin "6") (pinfunction "COMP_6") (pintype "input"))
    )
    (net (code "87") (name "Net-(U2-RT{slash}CLK)") (class "Default")
      (node (ref "R4") (pin "1") (pinfunction "1_1") (pintype "input"))
      (node (ref "U2") (pin "4") (pinfunction "RT/CLK_4") (pintype "input"))
    )
    (net (code "88") (name "Net-(U2-SW)") (class "Default")
      (node (ref "C4") (pin "2") (pinfunction "2_2") (pintype "input"))
      (node (ref "L1") (pin "1") (pinfunction "1_1") (pintype "input"))
      (node (ref "U2") (pin "8") (pinfunction "SW_8") (pintype "input"))
    )
    (net (code "89") (name "Net-(U3-VIN)") (class "Default")
      (node (ref "C10") (pin "1") (pinfunction "1_1") (pintype "input"))
      (node (ref "C9") (pin "1") (pinfunction "1_1") (pintype "input"))
      (node (ref "D2") (pin "K") (pinfunction "K_K") (pintype "input"))
      (node (ref "U3") (pin "1") (pinfunction "VIN_1") (pintype "input"))
    )
    (net (code "90") (name "Net-(电磁运放模块1-IN1)") (class "Default")
      (node (ref "电磁接口2") (pin "1") (pinfunction "1_1") (pintype "input"))
      (node (ref "电磁运放模块1") (pin "6") (pinfunction "IN1_6") (pintype "input"))
    )
    (net (code "91") (name "Net-(电磁运放模块1-IN2)") (class "Default")
      (node (ref "电磁接口2") (pin "3") (pinfunction "3_3") (pintype "input"))
      (node (ref "电磁运放模块1") (pin "4") (pinfunction "IN2_4") (pintype "input"))
    )
    (net (code "92") (name "Net-(电磁运放模块1-IN3)") (class "Default")
      (node (ref "电磁接口2") (pin "4") (pinfunction "4_4") (pintype "input"))
      (node (ref "电磁运放模块1") (pin "3") (pinfunction "IN3_3") (pintype "input"))
    )
    (net (code "93") (name "Net-(电磁运放模块1-IN4)") (class "Default")
      (node (ref "电磁接口2") (pin "6") (pinfunction "6_6") (pintype "input"))
      (node (ref "电磁运放模块1") (pin "1") (pinfunction "IN4_1") (pintype "input"))
    )
    (net (code "94") (name "VCC3V3") (class "Default")
      (node (ref "C15") (pin "1") (pinfunction "1_1") (pintype "input"))
      (node (ref "C16") (pin "1") (pinfunction "1_1") (pintype "input"))
      (node (ref "R12") (pin "1") (pinfunction "1_1") (pintype "input"))
      (node (ref "R14") (pin "1") (pinfunction "1_1") (pintype "input"))
      (node (ref "R15") (pin "1") (pinfunction "1_1") (pintype "input"))
      (node (ref "R16") (pin "1") (pinfunction "1_1") (pintype "input"))
      (node (ref "R17") (pin "1") (pinfunction "1_1") (pintype "input"))
      (node (ref "R22") (pin "1") (pinfunction "1_1") (pintype "input"))
      (node (ref "U4") (pin "5") (pinfunction "OUT_5") (pintype "input"))
      (node (ref "停车检测") (pin "2") (pinfunction "2_2") (pintype "input"))
      (node (ref "姿态传感器") (pin "1") (pinfunction "1_1") (pintype "input"))
      (node (ref "屏幕接口") (pin "4") (pinfunction "4_4") (pintype "input"))
      (node (ref "编码器1") (pin "2") (pinfunction "2_2") (pintype "input"))
      (node (ref "编码器2") (pin "2") (pinfunction "2_2") (pintype "input"))
    )
    (net (code "95") (name "VCC5V") (class "Default")
      (node (ref "C11") (pin "1") (pinfunction "1_1") (pintype "input"))
      (node (ref "C12") (pin "1") (pinfunction "1_1") (pintype "input"))
      (node (ref "C13") (pin "1") (pinfunction "1_1") (pintype "input"))
      (node (ref "C14") (pin "1") (pinfunction "1_1") (pintype "input"))
      (node (ref "C17") (pin "1") (pinfunction "1_1") (pintype "input"))
      (node (ref "C18") (pin "1") (pinfunction "1_1") (pintype "input"))
      (node (ref "C21") (pin "1") (pinfunction "1_1") (pintype "input"))
      (node (ref "C22") (pin "1") (pinfunction "1_1") (pintype "input"))
      (node (ref "R11") (pin "1") (pinfunction "1_1") (pintype "input"))
      (node (ref "U3") (pin "3") (pinfunction "VOUT_3") (pintype "input"))
      (node (ref "U4") (pin "1") (pinfunction "IN_1") (pintype "input"))
      (node (ref "U4") (pin "3") (pinfunction "EN_3") (pintype "input"))
      (node (ref "U5") (pin "1") (pinfunction "IN_1") (pintype "input"))
      (node (ref "U5") (pin "3") (pinfunction "EN_3") (pintype "input"))
      (node (ref "U6") (pin "1") (pinfunction "IN_1") (pintype "input"))
      (node (ref "U6") (pin "3") (pinfunction "EN_3") (pintype "input"))
      (node (ref "U7") (pin "5") (pinfunction "5V_5") (pintype "input"))
      (node (ref "U7") (pin "6") (pinfunction "5V_6") (pintype "input"))
      (node (ref "有去") (pin "1") (pinfunction "1_1") (pintype "input"))
      (node (ref "有来") (pin "1") (pinfunction "1_1") (pintype "input"))
      (node (ref "蓝牙串口模块1") (pin "7") (pinfunction "7_7") (pintype "input"))
    )
    (net (code "96") (name "VCCBAT") (class "Default")
      (node (ref "C1") (pin "1") (pinfunction "1_1") (pintype "input"))
      (node (ref "C2") (pin "1") (pinfunction "1_1") (pintype "input"))
      (node (ref "C3") (pin "1") (pinfunction "1_1") (pintype "input"))
      (node (ref "D2") (pin "A") (pinfunction "A_A") (pintype "input"))
      (node (ref "DCOUT1") (pin "1") (pinfunction "1_1") (pintype "input"))
      (node (ref "Q1") (pin "1") (pinfunction "D_1") (pintype "input"))
      (node (ref "U2") (pin "2") (pinfunction "VIN_2") (pintype "input"))
      (node (ref "U2") (pin "3") (pinfunction "EN_3") (pintype "input"))
    )
    (net (code "97") (name "VCCCAM") (class "Default")
      (node (ref "C19") (pin "1") (pinfunction "1_1") (pintype "input"))
      (node (ref "C20") (pin "1") (pinfunction "1_1") (pintype "input"))
      (node (ref "R13") (pin "1") (pinfunction "1_1") (pintype "input"))
      (node (ref "U5") (pin "5") (pinfunction "OUT_5") (pintype "input"))
      (node (ref "摄像头接口") (pin "16") (pinfunction "16_16") (pintype "input"))
    )
    (net (code "98") (name "VCCOP") (class "Default")
      (node (ref "C23") (pin "1") (pinfunction "1_1") (pintype "input"))
      (node (ref "C24") (pin "1") (pinfunction "1_1") (pintype "input"))
      (node (ref "R33") (pin "1") (pinfunction "1_1") (pintype "input"))
      (node (ref "U6") (pin "5") (pinfunction "OUT_5") (pintype "input"))
      (node (ref "电磁运放模块1") (pin "8") (pinfunction "VCC_8") (pintype "input"))
    )
    (net (code "99") (name "VCCSTEER") (class "Default")
      (node (ref "C5") (pin "1") (pinfunction "1_1") (pintype "input"))
      (node (ref "C6") (pin "1") (pinfunction "1_1") (pintype "input"))
      (node (ref "L1") (pin "2") (pinfunction "2_2") (pintype "input"))
      (node (ref "R6") (pin "1") (pinfunction "1_1") (pintype "input"))
      (node (ref "R9") (pin "2") (pinfunction "2_2") (pintype "input"))
      (node (ref "STEER1") (pin "2") (pinfunction "2_2") (pintype "input"))
    )
    (net (code "100") (name "unconnected-(M1-Pad1)") (class "Default")
      (node (ref "M1") (pin "1") (pinfunction "1_1") (pintype "input+no_connect"))
    )
    (net (code "101") (name "unconnected-(M2-Pad1)") (class "Default")
      (node (ref "M2") (pin "1") (pinfunction "1_1") (pintype "input+no_connect"))
    )
    (net (code "102") (name "unconnected-(M3-Pad1)") (class "Default")
      (node (ref "M3") (pin "1") (pinfunction "1_1") (pintype "input+no_connect"))
    )
    (net (code "103") (name "unconnected-(M4-Pad1)") (class "Default")
      (node (ref "M4") (pin "1") (pinfunction "1_1") (pintype "input+no_connect"))
    )
    (net (code "104") (name "unconnected-(U4-NC-Pad4)") (class "Default")
      (node (ref "U4") (pin "4") (pinfunction "NC_4") (pintype "input+no_connect"))
    )
    (net (code "105") (name "unconnected-(U5-NC-Pad4)") (class "Default")
      (node (ref "U5") (pin "4") (pinfunction "NC_4") (pintype "input+no_connect"))
    )
    (net (code "106") (name "unconnected-(U6-NC-Pad4)") (class "Default")
      (node (ref "U6") (pin "4") (pinfunction "NC_4") (pintype "input+no_connect"))
    )
    (net (code "107") (name "unconnected-(U7-3V3-Pad3)") (class "Default")
      (node (ref "U7") (pin "3") (pinfunction "3V3_3") (pintype "input+no_connect"))
    )
    (net (code "108") (name "unconnected-(U7-3V3-Pad4)") (class "Default")
      (node (ref "U7") (pin "4") (pinfunction "3V3_4") (pintype "input+no_connect"))
    )
    (net (code "109") (name "unconnected-(U7-B10-Pad59)") (class "Default")
      (node (ref "U7") (pin "59") (pinfunction "B10_59") (pintype "input+no_connect"))
    )
    (net (code "110") (name "unconnected-(U7-B11-Pad62)") (class "Default")
      (node (ref "U7") (pin "62") (pinfunction "B11_62") (pintype "input+no_connect"))
    )
    (net (code "111") (name "unconnected-(U7-B14-Pad63)") (class "Default")
      (node (ref "U7") (pin "63") (pinfunction "B14_63") (pintype "input+no_connect"))
    )
    (net (code "112") (name "unconnected-(U7-C2-Pad36)") (class "Default")
      (node (ref "U7") (pin "36") (pinfunction "C2_36") (pintype "input+no_connect"))
    )
    (net (code "113") (name "unconnected-(U7-C3-Pad37)") (class "Default")
      (node (ref "U7") (pin "37") (pinfunction "C3_37") (pintype "input+no_connect"))
    )
    (net (code "114") (name "unconnected-(U7-C4-Pad46)") (class "Default")
      (node (ref "U7") (pin "46") (pinfunction "C4_46") (pintype "input+no_connect"))
    )
    (net (code "115") (name "unconnected-(U7-C5-Pad47)") (class "Default")
      (node (ref "U7") (pin "47") (pinfunction "C5_47") (pintype "input+no_connect"))
    )
    (net (code "116") (name "unconnected-(U7-C6-Pad73)") (class "Default")
      (node (ref "U7") (pin "73") (pinfunction "C6_73") (pintype "input+no_connect"))
    )
    (net (code "117") (name "unconnected-(U7-C7-Pad76)") (class "Default")
      (node (ref "U7") (pin "76") (pinfunction "C7_76") (pintype "input+no_connect"))
    )
    (net (code "118") (name "unconnected-(U7-D1-Pad12)") (class "Default")
      (node (ref "U7") (pin "12") (pinfunction "D1_12") (pintype "input+no_connect"))
    )
    (net (code "119") (name "unconnected-(U7-D3-Pad14)") (class "Default")
      (node (ref "U7") (pin "14") (pinfunction "D3_14") (pintype "input+no_connect"))
    )
    (net (code "120") (name "unconnected-(U7-D5-Pad16)") (class "Default")
      (node (ref "U7") (pin "16") (pinfunction "D5_16") (pintype "input+no_connect"))
    )
    (net (code "121") (name "unconnected-(U7-D6-Pad17)") (class "Default")
      (node (ref "U7") (pin "17") (pinfunction "D6_17") (pintype "input+no_connect"))
    )
    (net (code "122") (name "unconnected-(U7-D12-Pad69)") (class "Default")
      (node (ref "U7") (pin "69") (pinfunction "D12_69") (pintype "input+no_connect"))
    )
    (net (code "123") (name "unconnected-(U7-D13-Pad72)") (class "Default")
      (node (ref "U7") (pin "72") (pinfunction "D13_72") (pintype "input+no_connect"))
    )
    (net (code "124") (name "unconnected-(U7-D14-Pad71)") (class "Default")
      (node (ref "U7") (pin "71") (pinfunction "D14_71") (pintype "input+no_connect"))
    )
    (net (code "125") (name "unconnected-(U7-D15-Pad74)") (class "Default")
      (node (ref "U7") (pin "74") (pinfunction "D15_74") (pintype "input+no_connect"))
    )
    (net (code "126") (name "unconnected-(U7-E10-Pad53)") (class "Default")
      (node (ref "U7") (pin "53") (pinfunction "E10_53") (pintype "input+no_connect"))
    )
    (net (code "127") (name "unconnected-(姿态传感器-Pad7)") (class "Default")
      (node (ref "姿态传感器") (pin "7") (pinfunction "7_7") (pintype "input+no_connect"))
    )
    (net (code "128") (name "unconnected-(姿态传感器-Pad8)") (class "Default")
      (node (ref "姿态传感器") (pin "8") (pinfunction "8_8") (pintype "input+no_connect"))
    )
    (net (code "129") (name "unconnected-(有去-Pad4)") (class "Default")
      (node (ref "有去") (pin "4") (pinfunction "4_4") (pintype "input+no_connect"))
    )
    (net (code "130") (name "unconnected-(编码器1-Pad5)") (class "Default")
      (node (ref "编码器1") (pin "5") (pinfunction "5_5") (pintype "input+no_connect"))
    )
    (net (code "131") (name "unconnected-(编码器1-Pad6)") (class "Default")
      (node (ref "编码器1") (pin "6") (pinfunction "6_6") (pintype "input+no_connect"))
    )
    (net (code "132") (name "unconnected-(编码器2-Pad5)") (class "Default")
      (node (ref "编码器2") (pin "5") (pinfunction "5_5") (pintype "input+no_connect"))
    )
    (net (code "133") (name "unconnected-(编码器2-Pad6)") (class "Default")
      (node (ref "编码器2") (pin "6") (pinfunction "6_6") (pintype "input+no_connect"))
    )
    (net (code "134") (name "unconnected-(蓝牙串口模块1-Pad2)") (class "Default")
      (node (ref "蓝牙串口模块1") (pin "2") (pinfunction "2_2") (pintype "input+no_connect"))
    )
    (net (code "135") (name "unconnected-(蓝牙串口模块1-Pad8)") (class "Default")
      (node (ref "蓝牙串口模块1") (pin "8") (pinfunction "8_8") (pintype "input+no_connect"))
    )
  )
)
